# ATTinyServoSMT_v11.net
KiCad netlist of a schematic drawn in EAGLE
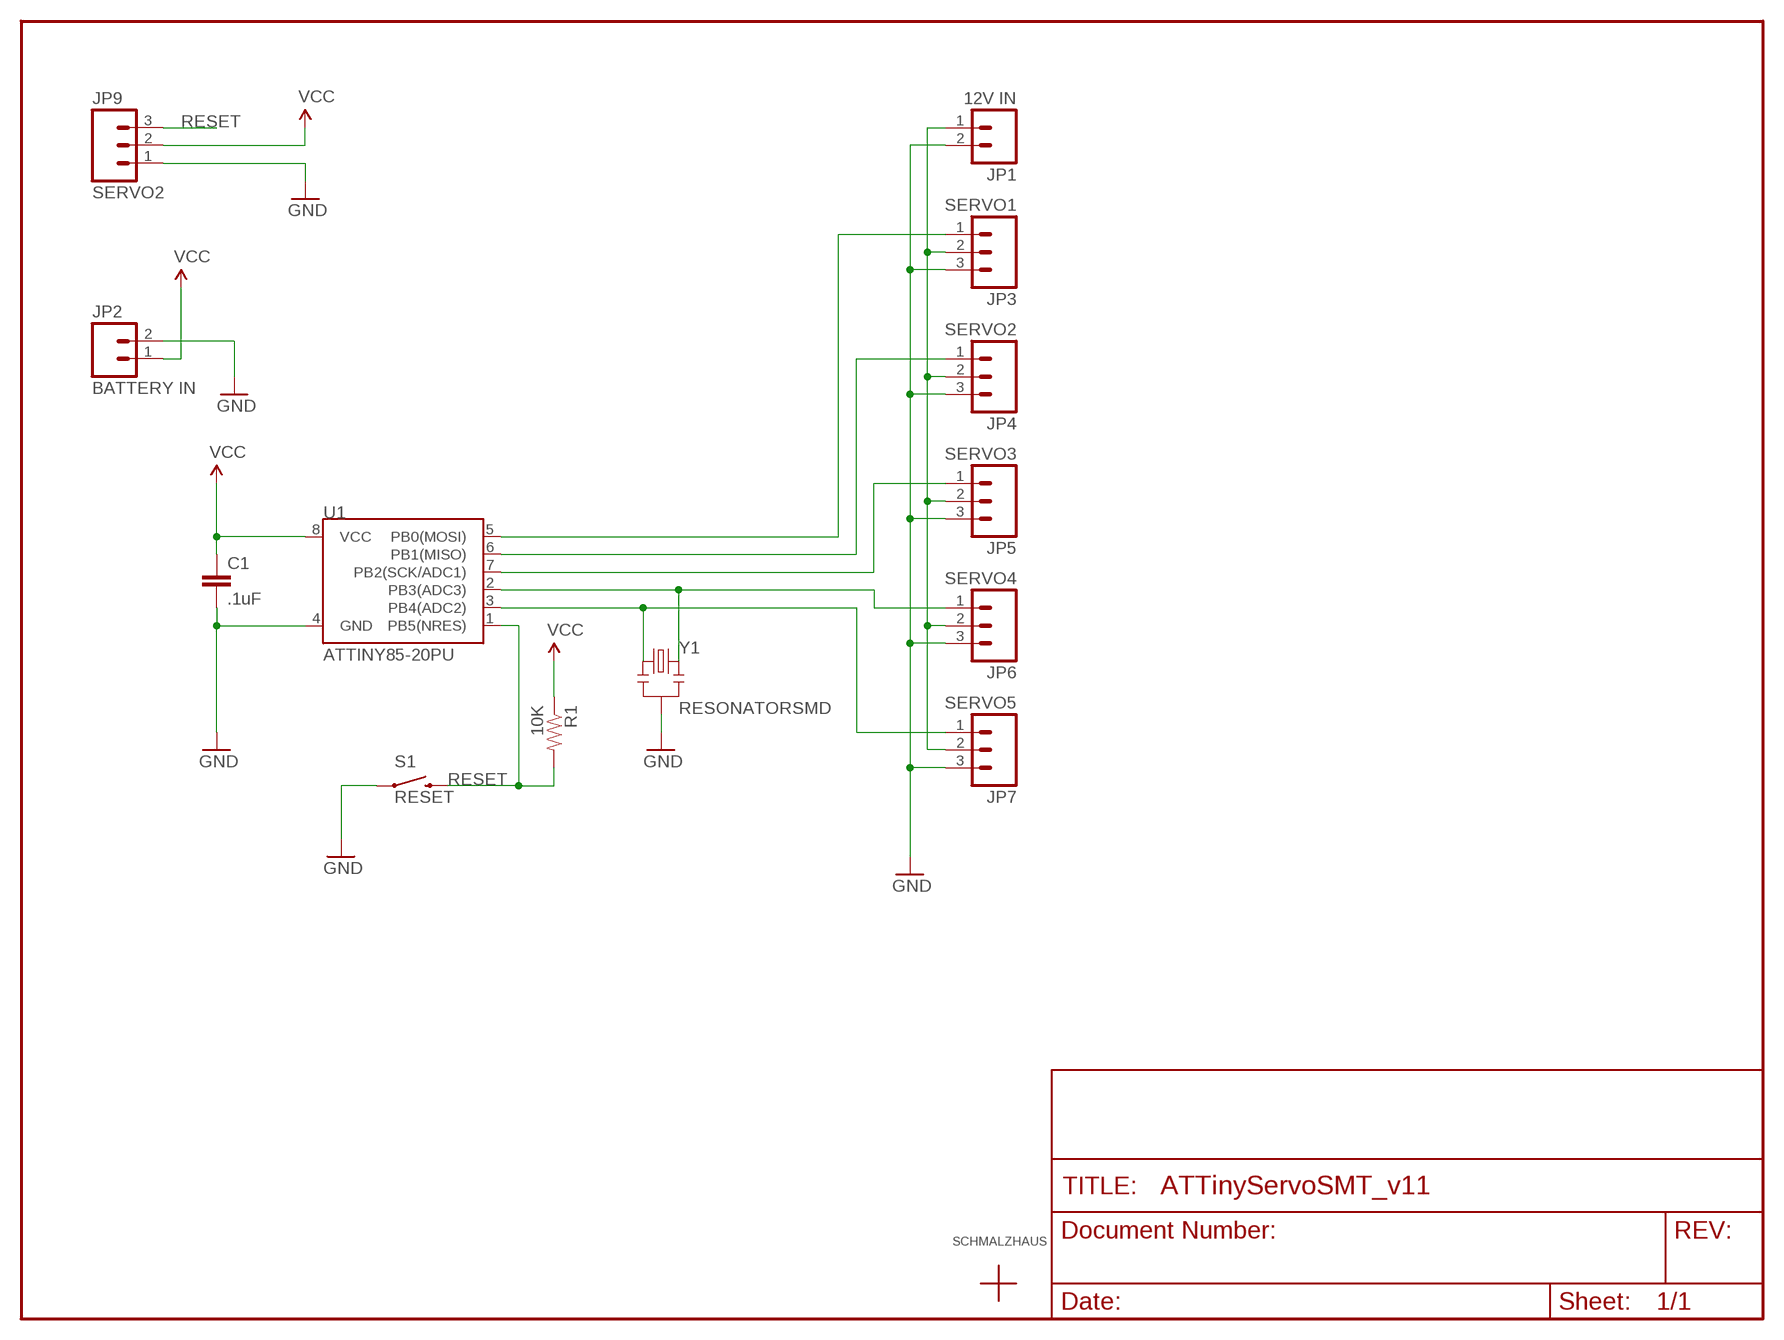
[diagram p0: schematic, sheet 1]

(export (version "E")
  (design (tool "Eeschema 10.0.6"))
  (components
    (comp (ref "C1")
      (value ".1uF")
      (footprint "eagle-import:0603-CAP")
      (libsource (lib "eagle-import") (part "CAP0603-CAP"))
    )
    (comp (ref "JP1")
      (value "12V IN")
      (footprint "eagle-import:SCREWTERMINAL-3.5MM-2")
      (libsource (lib "eagle-import") (part "M023.5MM"))
    )
    (comp (ref "JP2")
      (value "BATTERY IN")
      (footprint "eagle-import:SCREWTERMINAL-3.5MM-2")
      (libsource (lib "eagle-import") (part "M023.5MM"))
    )
    (comp (ref "JP3")
      (value "SERVO1")
      (footprint "eagle-import:1X03")
      (libsource (lib "eagle-import") (part "M03PTH"))
    )
    (comp (ref "JP4")
      (value "SERVO2")
      (footprint "eagle-import:1X03")
      (libsource (lib "eagle-import") (part "M03PTH"))
    )
    (comp (ref "JP5")
      (value "SERVO3")
      (footprint "eagle-import:1X03")
      (libsource (lib "eagle-import") (part "M03PTH"))
    )
    (comp (ref "JP6")
      (value "SERVO4")
      (footprint "eagle-import:1X03")
      (libsource (lib "eagle-import") (part "M03PTH"))
    )
    (comp (ref "JP7")
      (value "SERVO5")
      (footprint "eagle-import:1X03")
      (libsource (lib "eagle-import") (part "M03PTH"))
    )
    (comp (ref "JP9")
      (value "SERVO2")
      (footprint "eagle-import:1X03")
      (libsource (lib "eagle-import") (part "M03PTH"))
    )
    (comp (ref "R1")
      (value "10K")
      (footprint "eagle-import:0603-RES")
      (libsource (lib "eagle-import") (part "RESISTOR0603-RES"))
    )
    (comp (ref "S1")
      (value "RESET")
      (footprint "eagle-import:TACTILE_SWITCH_SMD")
      (libsource (lib "eagle-import") (part "SWITCH-MOMENTARY-2SMD"))
    )
    (comp (ref "U$1")
      (value "SCHMALZHAUSSCHMALZHAUS_SMALL")
      (footprint "eagle-import:SCHMALZHAUS_SMALL")
      (libsource (lib "eagle-import") (part "SCHMALZHAUSSCHMALZHAUS_SMALL"))
    )
    (comp (ref "U1")
      (value "ATTINY85-20PU")
      (footprint "eagle-import:SO08-EIAJ")
      (libsource (lib "eagle-import") (part "ATTINY45"))
    )
    (comp (ref "Y1")
      (value "RESONATORSMD")
      (footprint "eagle-import:RESONATOR-SMD")
      (libsource (lib "eagle-import") (part "RESONATORSMD"))
    )
  )
  (nets
    (net (code "1") (name "/RESET") (class "Default")
      (node (ref "JP9") (pin "3") (pinfunction "3_3") (pintype "passive"))
      (node (ref "R1") (pin "2") (pinfunction "2_2") (pintype "passive"))
      (node (ref "S1") (pin "3") (pinfunction "2_3") (pintype "passive"))
      (node (ref "U1") (pin "1") (pinfunction "PB5(NRES)_1") (pintype "bidirectional"))
    )
    (net (code "2") (name "GND") (class "Default")
      (node (ref "C1") (pin "2") (pinfunction "2_2") (pintype "passive"))
      (node (ref "JP1") (pin "2") (pinfunction "2_2") (pintype "passive"))
      (node (ref "JP2") (pin "2") (pinfunction "2_2") (pintype "passive"))
      (node (ref "JP3") (pin "3") (pinfunction "3_3") (pintype "passive"))
      (node (ref "JP4") (pin "3") (pinfunction "3_3") (pintype "passive"))
      (node (ref "JP5") (pin "3") (pinfunction "3_3") (pintype "passive"))
      (node (ref "JP6") (pin "3") (pinfunction "3_3") (pintype "passive"))
      (node (ref "JP7") (pin "3") (pinfunction "3_3") (pintype "passive"))
      (node (ref "JP9") (pin "1") (pinfunction "1_1") (pintype "passive"))
      (node (ref "S1") (pin "1") (pinfunction "1_1") (pintype "passive"))
      (node (ref "U1") (pin "4") (pinfunction "GND_4") (pintype "bidirectional"))
      (node (ref "Y1") (pin "2") (pinfunction "2_2") (pintype "passive"))
    )
    (net (code "3") (name "Net-(JP1-Pad1)") (class "Default")
      (node (ref "JP1") (pin "1") (pinfunction "1_1") (pintype "passive"))
      (node (ref "JP3") (pin "2") (pinfunction "2_2") (pintype "passive"))
      (node (ref "JP4") (pin "2") (pinfunction "2_2") (pintype "passive"))
      (node (ref "JP5") (pin "2") (pinfunction "2_2") (pintype "passive"))
      (node (ref "JP6") (pin "2") (pinfunction "2_2") (pintype "passive"))
      (node (ref "JP7") (pin "2") (pinfunction "2_2") (pintype "passive"))
    )
    (net (code "4") (name "Net-(U1-PB0(MOSI))") (class "Default")
      (node (ref "JP3") (pin "1") (pinfunction "1_1") (pintype "passive"))
      (node (ref "U1") (pin "5") (pinfunction "PB0(MOSI)_5") (pintype "bidirectional"))
    )
    (net (code "5") (name "Net-(U1-PB1(MISO))") (class "Default")
      (node (ref "JP4") (pin "1") (pinfunction "1_1") (pintype "passive"))
      (node (ref "U1") (pin "6") (pinfunction "PB1(MISO)_6") (pintype "bidirectional"))
    )
    (net (code "6") (name "Net-(U1-PB2(SCK{slash}ADC1))") (class "Default")
      (node (ref "JP5") (pin "1") (pinfunction "1_1") (pintype "passive"))
      (node (ref "U1") (pin "7") (pinfunction "PB2(SCK/ADC1)_7") (pintype "bidirectional"))
    )
    (net (code "7") (name "Net-(U1-PB3(ADC3))") (class "Default")
      (node (ref "JP6") (pin "1") (pinfunction "1_1") (pintype "passive"))
      (node (ref "U1") (pin "2") (pinfunction "PB3(ADC3)_2") (pintype "bidirectional"))
      (node (ref "Y1") (pin "3") (pinfunction "3_3") (pintype "passive"))
    )
    (net (code "8") (name "Net-(U1-PB4(ADC2))") (class "Default")
      (node (ref "JP7") (pin "1") (pinfunction "1_1") (pintype "passive"))
      (node (ref "U1") (pin "3") (pinfunction "PB4(ADC2)_3") (pintype "bidirectional"))
      (node (ref "Y1") (pin "1") (pinfunction "1_1") (pintype "passive"))
    )
    (net (code "9") (name "VCC") (class "Default")
      (node (ref "C1") (pin "1") (pinfunction "1_1") (pintype "passive"))
      (node (ref "JP2") (pin "1") (pinfunction "1_1") (pintype "passive"))
      (node (ref "JP9") (pin "2") (pinfunction "2_2") (pintype "passive"))
      (node (ref "R1") (pin "1") (pinfunction "1_1") (pintype "passive"))
      (node (ref "U1") (pin "8") (pinfunction "VCC_8") (pintype "bidirectional"))
    )
  )
)
